# WT2_Sensors.net
KiCad netlist of a schematic drawn in Altium Designer
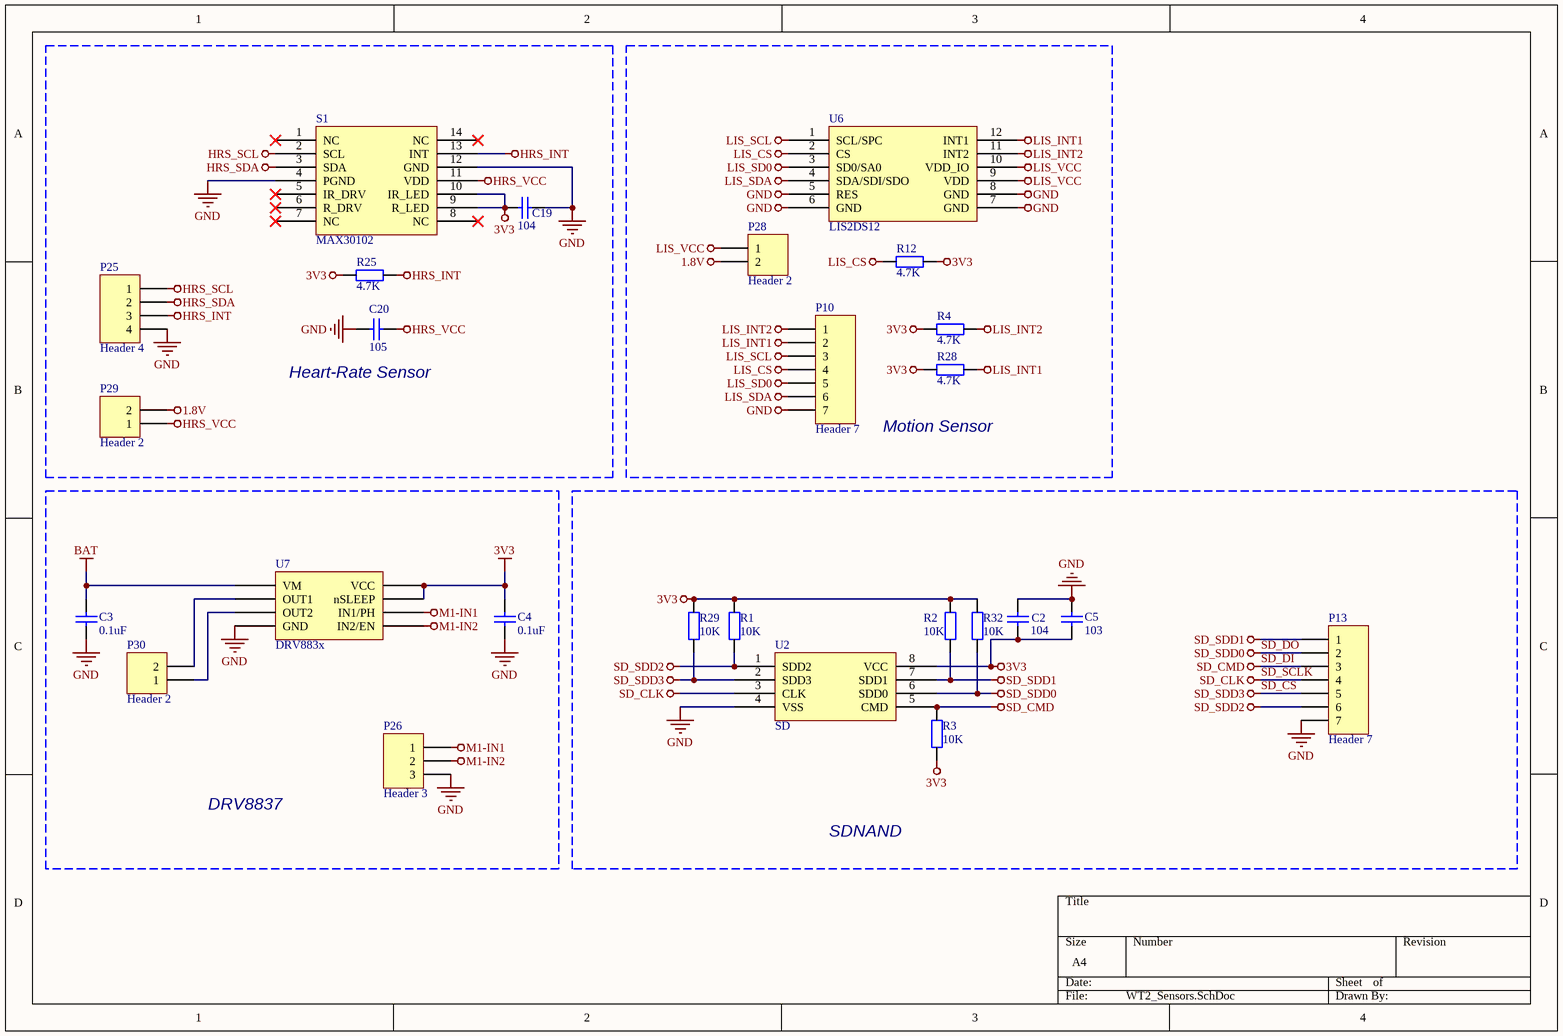
[diagram p0: WT2_Sensors.SchDoc]

(export (version "E")
  (design (tool "Eeschema 10.0.6"))
  (components
    (comp (ref "C2")
      (value "104")
      (footprint "电容_C0603")
      (fields (field (name "C") "104"))
      (libsource (lib "元件库") (part "cap"))
    )
    (comp (ref "C3")
      (value "0.1uF")
      (footprint "电容_C0603")
      (fields (field (name "C") "0.1uF"))
      (libsource (lib "元件库") (part "cap"))
    )
    (comp (ref "C4")
      (value "0.1uF")
      (footprint "电容_C0603")
      (fields (field (name "C") "0.1uF"))
      (libsource (lib "元件库") (part "cap"))
    )
    (comp (ref "C5")
      (value "103")
      (footprint "电容_C0603")
      (fields (field (name "C") "103"))
      (libsource (lib "元件库") (part "cap"))
    )
    (comp (ref "C19")
      (value "104")
      (footprint "电容_C0603")
      (fields (field (name "C") "104"))
      (libsource (lib "元件库") (part "cap"))
    )
    (comp (ref "C20")
      (value "105")
      (footprint "电容_C0603")
      (fields (field (name "C") "105"))
      (libsource (lib "元件库") (part "cap"))
    )
    (comp (ref "P10")
      (value "Header 7")
      (footprint "HDR1X7")
      (description "Header, 7-Pin")
      (fields (field (name "PUBLISHER") "Altium Limited"))
      (libsource (lib "Miscellaneous Connectors") (part "Header 7"))
    )
    (comp (ref "P13")
      (value "Header 7")
      (footprint "HDR1X7")
      (description "Header, 7-Pin")
      (fields (field (name "PUBLISHER") "Altium Limited"))
      (libsource (lib "Miscellaneous Connectors") (part "Header 7"))
    )
    (comp (ref "P25")
      (value "Header 4")
      (footprint "HDR1X4")
      (description "Header, 4-Pin")
      (fields (field (name "PUBLISHER") "Altium Limited"))
      (libsource (lib "Miscellaneous Connectors") (part "Header 4"))
    )
    (comp (ref "P26")
      (value "Header 3")
      (footprint "HDR1X3")
      (description "Header, 3-Pin")
      (fields (field (name "PUBLISHER") "Altium Limited"))
      (libsource (lib "Miscellaneous Connectors") (part "Header 3"))
    )
    (comp (ref "P28")
      (value "Header 2")
      (footprint "HDR1X2")
      (description "Header, 2-Pin")
      (fields (field (name "PUBLISHER") "Altium Limited"))
      (libsource (lib "") (part "Header 2_1"))
    )
    (comp (ref "P29")
      (value "Header 2")
      (footprint "HDR1X2")
      (description "Header, 2-Pin")
      (fields (field (name "PUBLISHER") "Altium Limited"))
      (libsource (lib "Miscellaneous Connectors") (part "Header 2"))
    )
    (comp (ref "P30")
      (value "Header 2")
      (footprint "HDR1X2")
      (description "Header, 2-Pin")
      (fields (field (name "PUBLISHER") "Altium Limited"))
      (libsource (lib "Miscellaneous Connectors") (part "Header 2"))
    )
    (comp (ref "R1")
      (value "10K")
      (footprint "电阻_R0603")
      (fields (field (name "R") "10K"))
      (libsource (lib "") (part "Res_1"))
    )
    (comp (ref "R2")
      (value "10K")
      (footprint "电阻_R0603")
      (fields (field (name "R") "10K"))
      (libsource (lib "") (part "Res_1"))
    )
    (comp (ref "R3")
      (value "10K")
      (footprint "电阻_R0603")
      (fields (field (name "R") "10K"))
      (libsource (lib "") (part "Res_1"))
    )
    (comp (ref "R4")
      (value "4.7K")
      (footprint "电阻_R0603")
      (fields (field (name "R") "4.7K"))
      (libsource (lib "元件库") (part "Res"))
    )
    (comp (ref "R12")
      (value "4.7K")
      (footprint "电阻_R0603")
      (fields (field (name "R") "4.7K"))
      (libsource (lib "元件库") (part "Res"))
    )
    (comp (ref "R25")
      (value "4.7K")
      (footprint "电阻_R0603")
      (fields (field (name "R") "4.7K"))
      (libsource (lib "元件库") (part "Res"))
    )
    (comp (ref "R28")
      (value "4.7K")
      (footprint "电阻_R0603")
      (fields (field (name "R") "4.7K"))
      (libsource (lib "元件库") (part "Res"))
    )
    (comp (ref "R29")
      (value "10K")
      (footprint "电阻_R0603")
      (fields (field (name "R") "10K"))
      (libsource (lib "") (part "Res_1"))
    )
    (comp (ref "R32")
      (value "10K")
      (footprint "电阻_R0603")
      (fields (field (name "R") "10K"))
      (libsource (lib "") (part "Res_1"))
    )
    (comp (ref "S1")
      (value "MAX30102")
      (footprint "TriggersLib:MAX30102")
      (description "血氧浓度传感器")
      (libsource (lib "TriggersLib") (part "MAX30102"))
    )
    (comp (ref "U2") (value "SD") (footprint "LGA-8_6*8mm2") (libsource (lib "TriggersLib") (part "SDNAND")))
    (comp (ref "U6")
      (value "LIS2DS12")
      (footprint "TriggersLib:LGA-12_2*2mm")
      (description "运动传感器")
      (libsource (lib "TriggersLib") (part "LIS2DS12"))
    )
    (comp (ref "U7")
      (value "DRV883x")
      (footprint "TriggersLib:WSON-8_2*2")
      (libsource (lib "xSchlib") (part "DRV883x"))
    )
  )
  (nets
    (net (code "1") (name "1.8V") (class "Default")
      (node (ref "P28") (pin "2") (pinfunction "2_2") (pintype "passive"))
      (node (ref "P29") (pin "2") (pinfunction "2_2") (pintype "passive"))
    )
    (net (code "2") (name "3V3") (class "Default")
      (node (ref "C19") (pin "2") (pinfunction "2_2") (pintype "passive"))
      (node (ref "C2") (pin "1") (pinfunction "1_1") (pintype "passive"))
      (node (ref "C4") (pin "2") (pinfunction "2_2") (pintype "passive"))
      (node (ref "C5") (pin "1") (pinfunction "1_1") (pintype "passive"))
      (node (ref "R1") (pin "1") (pinfunction "1_1") (pintype "passive"))
      (node (ref "R12") (pin "1") (pinfunction "1_1") (pintype "passive"))
      (node (ref "R2") (pin "1") (pinfunction "1_1") (pintype "passive"))
      (node (ref "R25") (pin "2") (pinfunction "2_2") (pintype "passive"))
      (node (ref "R28") (pin "2") (pinfunction "2_2") (pintype "passive"))
      (node (ref "R29") (pin "1") (pinfunction "1_1") (pintype "passive"))
      (node (ref "R3") (pin "2") (pinfunction "2_2") (pintype "passive"))
      (node (ref "R32") (pin "1") (pinfunction "1_1") (pintype "passive"))
      (node (ref "R4") (pin "2") (pinfunction "2_2") (pintype "passive"))
      (node (ref "S1") (pin "10") (pinfunction "IR_LED_10") (pintype "passive"))
      (node (ref "S1") (pin "9") (pinfunction "R_LED_9") (pintype "passive"))
      (node (ref "U2") (pin "8") (pinfunction "VCC_8") (pintype "passive"))
      (node (ref "U7") (pin "7") (pinfunction "nSLEEP_7") (pintype "passive"))
      (node (ref "U7") (pin "8") (pinfunction "VCC_8") (pintype "passive"))
    )
    (net (code "3") (name "BAT") (class "Default")
      (node (ref "C3") (pin "1") (pinfunction "1_1") (pintype "passive"))
      (node (ref "U7") (pin "1") (pinfunction "VM_1") (pintype "passive"))
    )
    (net (code "4") (name "GND") (class "Default")
      (node (ref "C19") (pin "1") (pinfunction "1_1") (pintype "passive"))
      (node (ref "C2") (pin "2") (pinfunction "2_2") (pintype "passive"))
      (node (ref "C20") (pin "2") (pinfunction "2_2") (pintype "passive"))
      (node (ref "C3") (pin "2") (pinfunction "2_2") (pintype "passive"))
      (node (ref "C4") (pin "1") (pinfunction "1_1") (pintype "passive"))
      (node (ref "C5") (pin "2") (pinfunction "2_2") (pintype "passive"))
      (node (ref "P10") (pin "7") (pinfunction "7_7") (pintype "passive"))
      (node (ref "P13") (pin "7") (pinfunction "7_7") (pintype "passive"))
      (node (ref "P25") (pin "4") (pinfunction "4_4") (pintype "passive"))
      (node (ref "P26") (pin "3") (pinfunction "3_3") (pintype "passive"))
      (node (ref "S1") (pin "12") (pinfunction "GND_12") (pintype "passive"))
      (node (ref "S1") (pin "4") (pinfunction "PGND_4") (pintype "passive"))
      (node (ref "U2") (pin "4") (pinfunction "VSS_4") (pintype "passive"))
      (node (ref "U6") (pin "5") (pinfunction "RES_5") (pintype "passive"))
      (node (ref "U6") (pin "6") (pinfunction "GND_6") (pintype "passive"))
      (node (ref "U6") (pin "7") (pinfunction "GND_7") (pintype "passive"))
      (node (ref "U6") (pin "8") (pinfunction "GND_8") (pintype "passive"))
      (node (ref "U7") (pin "4") (pinfunction "GND_4") (pintype "passive"))
    )
    (net (code "5") (name "HRS_INT") (class "Default")
      (node (ref "P25") (pin "3") (pinfunction "3_3") (pintype "passive"))
      (node (ref "R25") (pin "1") (pinfunction "1_1") (pintype "passive"))
      (node (ref "S1") (pin "13") (pinfunction "INT_13") (pintype "passive"))
    )
    (net (code "6") (name "HRS_SCL") (class "Default")
      (node (ref "P25") (pin "1") (pinfunction "1_1") (pintype "passive"))
      (node (ref "S1") (pin "2") (pinfunction "SCL_2") (pintype "passive"))
    )
    (net (code "7") (name "HRS_SDA") (class "Default")
      (node (ref "P25") (pin "2") (pinfunction "2_2") (pintype "passive"))
      (node (ref "S1") (pin "3") (pinfunction "SDA_3") (pintype "passive"))
    )
    (net (code "8") (name "HRS_VCC") (class "Default")
      (node (ref "C20") (pin "1") (pinfunction "1_1") (pintype "passive"))
      (node (ref "P29") (pin "1") (pinfunction "1_1") (pintype "passive"))
      (node (ref "S1") (pin "11") (pinfunction "VDD_11") (pintype "passive"))
    )
    (net (code "9") (name "LIS_CS") (class "Default")
      (node (ref "P10") (pin "4") (pinfunction "4_4") (pintype "passive"))
      (node (ref "R12") (pin "2") (pinfunction "2_2") (pintype "passive"))
      (node (ref "U6") (pin "2") (pinfunction "CS_2") (pintype "passive"))
    )
    (net (code "10") (name "LIS_INT1") (class "Default")
      (node (ref "P10") (pin "2") (pinfunction "2_2") (pintype "passive"))
      (node (ref "R28") (pin "1") (pinfunction "1_1") (pintype "passive"))
      (node (ref "U6") (pin "12") (pinfunction "INT1_12") (pintype "passive"))
    )
    (net (code "11") (name "LIS_INT2") (class "Default")
      (node (ref "P10") (pin "1") (pinfunction "1_1") (pintype "passive"))
      (node (ref "R4") (pin "1") (pinfunction "1_1") (pintype "passive"))
      (node (ref "U6") (pin "11") (pinfunction "INT2_11") (pintype "passive"))
    )
    (net (code "12") (name "LIS_SCL") (class "Default")
      (node (ref "P10") (pin "3") (pinfunction "3_3") (pintype "passive"))
      (node (ref "U6") (pin "1") (pinfunction "SCL/SPC_1") (pintype "passive"))
    )
    (net (code "13") (name "LIS_SD0") (class "Default")
      (node (ref "P10") (pin "5") (pinfunction "5_5") (pintype "passive"))
      (node (ref "U6") (pin "3") (pinfunction "SD0/SA0_3") (pintype "passive"))
    )
    (net (code "14") (name "LIS_SDA") (class "Default")
      (node (ref "P10") (pin "6") (pinfunction "6_6") (pintype "passive"))
      (node (ref "U6") (pin "4") (pinfunction "SDA/SDI/SDO_4") (pintype "passive"))
    )
    (net (code "15") (name "LIS_VCC") (class "Default")
      (node (ref "P28") (pin "1") (pinfunction "1_1") (pintype "passive"))
      (node (ref "U6") (pin "10") (pinfunction "VDD_IO_10") (pintype "passive"))
      (node (ref "U6") (pin "9") (pinfunction "VDD_9") (pintype "passive"))
    )
    (net (code "16") (name "M1-IN1") (class "Default")
      (node (ref "P26") (pin "1") (pinfunction "1_1") (pintype "passive"))
      (node (ref "U7") (pin "6") (pinfunction "IN1/PH_6") (pintype "passive"))
    )
    (net (code "17") (name "M1-IN2") (class "Default")
      (node (ref "P26") (pin "2") (pinfunction "2_2") (pintype "passive"))
      (node (ref "U7") (pin "5") (pinfunction "IN2/EN_5") (pintype "passive"))
    )
    (net (code "18") (name "Net-(U7-OUT1)") (class "Default")
      (node (ref "P30") (pin "2") (pinfunction "2_2") (pintype "passive"))
      (node (ref "U7") (pin "2") (pinfunction "OUT1_2") (pintype "passive"))
    )
    (net (code "19") (name "Net-(U7-OUT2)") (class "Default")
      (node (ref "P30") (pin "1") (pinfunction "1_1") (pintype "passive"))
      (node (ref "U7") (pin "3") (pinfunction "OUT2_3") (pintype "passive"))
    )
    (net (code "20") (name "SD_CLK") (class "Default")
      (node (ref "P13") (pin "4") (pinfunction "4_4") (pintype "passive"))
      (node (ref "U2") (pin "3") (pinfunction "CLK_3") (pintype "passive"))
    )
    (net (code "21") (name "SD_CMD") (class "Default")
      (node (ref "P13") (pin "3") (pinfunction "3_3") (pintype "passive"))
      (node (ref "R3") (pin "1") (pinfunction "1_1") (pintype "passive"))
      (node (ref "U2") (pin "5") (pinfunction "CMD_5") (pintype "passive"))
    )
    (net (code "22") (name "SD_SDD0") (class "Default")
      (node (ref "P13") (pin "2") (pinfunction "2_2") (pintype "passive"))
      (node (ref "R32") (pin "2") (pinfunction "2_2") (pintype "passive"))
      (node (ref "U2") (pin "6") (pinfunction "SDD0_6") (pintype "passive"))
    )
    (net (code "23") (name "SD_SDD1") (class "Default")
      (node (ref "P13") (pin "1") (pinfunction "1_1") (pintype "passive"))
      (node (ref "R2") (pin "2") (pinfunction "2_2") (pintype "passive"))
      (node (ref "U2") (pin "7") (pinfunction "SDD1_7") (pintype "passive"))
    )
    (net (code "24") (name "SD_SDD2") (class "Default")
      (node (ref "P13") (pin "6") (pinfunction "6_6") (pintype "passive"))
      (node (ref "R1") (pin "2") (pinfunction "2_2") (pintype "passive"))
      (node (ref "U2") (pin "1") (pinfunction "SDD2_1") (pintype "passive"))
    )
    (net (code "25") (name "SD_SDD3") (class "Default")
      (node (ref "P13") (pin "5") (pinfunction "5_5") (pintype "passive"))
      (node (ref "R29") (pin "2") (pinfunction "2_2") (pintype "passive"))
      (node (ref "U2") (pin "2") (pinfunction "SDD3_2") (pintype "passive"))
    )
    (net (code "26") (name "unconnected-(S1-IR_DRV-Pad5)") (class "Default")
      (node (ref "S1") (pin "5") (pinfunction "IR_DRV_5") (pintype "passive+no_connect"))
    )
    (net (code "27") (name "unconnected-(S1-NC-Pad1)") (class "Default")
      (node (ref "S1") (pin "1") (pinfunction "NC_1") (pintype "passive+no_connect"))
    )
    (net (code "28") (name "unconnected-(S1-NC-Pad7)") (class "Default")
      (node (ref "S1") (pin "7") (pinfunction "NC_7") (pintype "passive+no_connect"))
    )
    (net (code "29") (name "unconnected-(S1-NC-Pad8)") (class "Default")
      (node (ref "S1") (pin "8") (pinfunction "NC_8") (pintype "passive+no_connect"))
    )
    (net (code "30") (name "unconnected-(S1-NC-Pad14)") (class "Default")
      (node (ref "S1") (pin "14") (pinfunction "NC_14") (pintype "passive+no_connect"))
    )
    (net (code "31") (name "unconnected-(S1-R_DRV-Pad6)") (class "Default")
      (node (ref "S1") (pin "6") (pinfunction "R_DRV_6") (pintype "passive+no_connect"))
    )
  )
)
